# v2.net
KiCad netlist of a schematic drawn in EAGLE
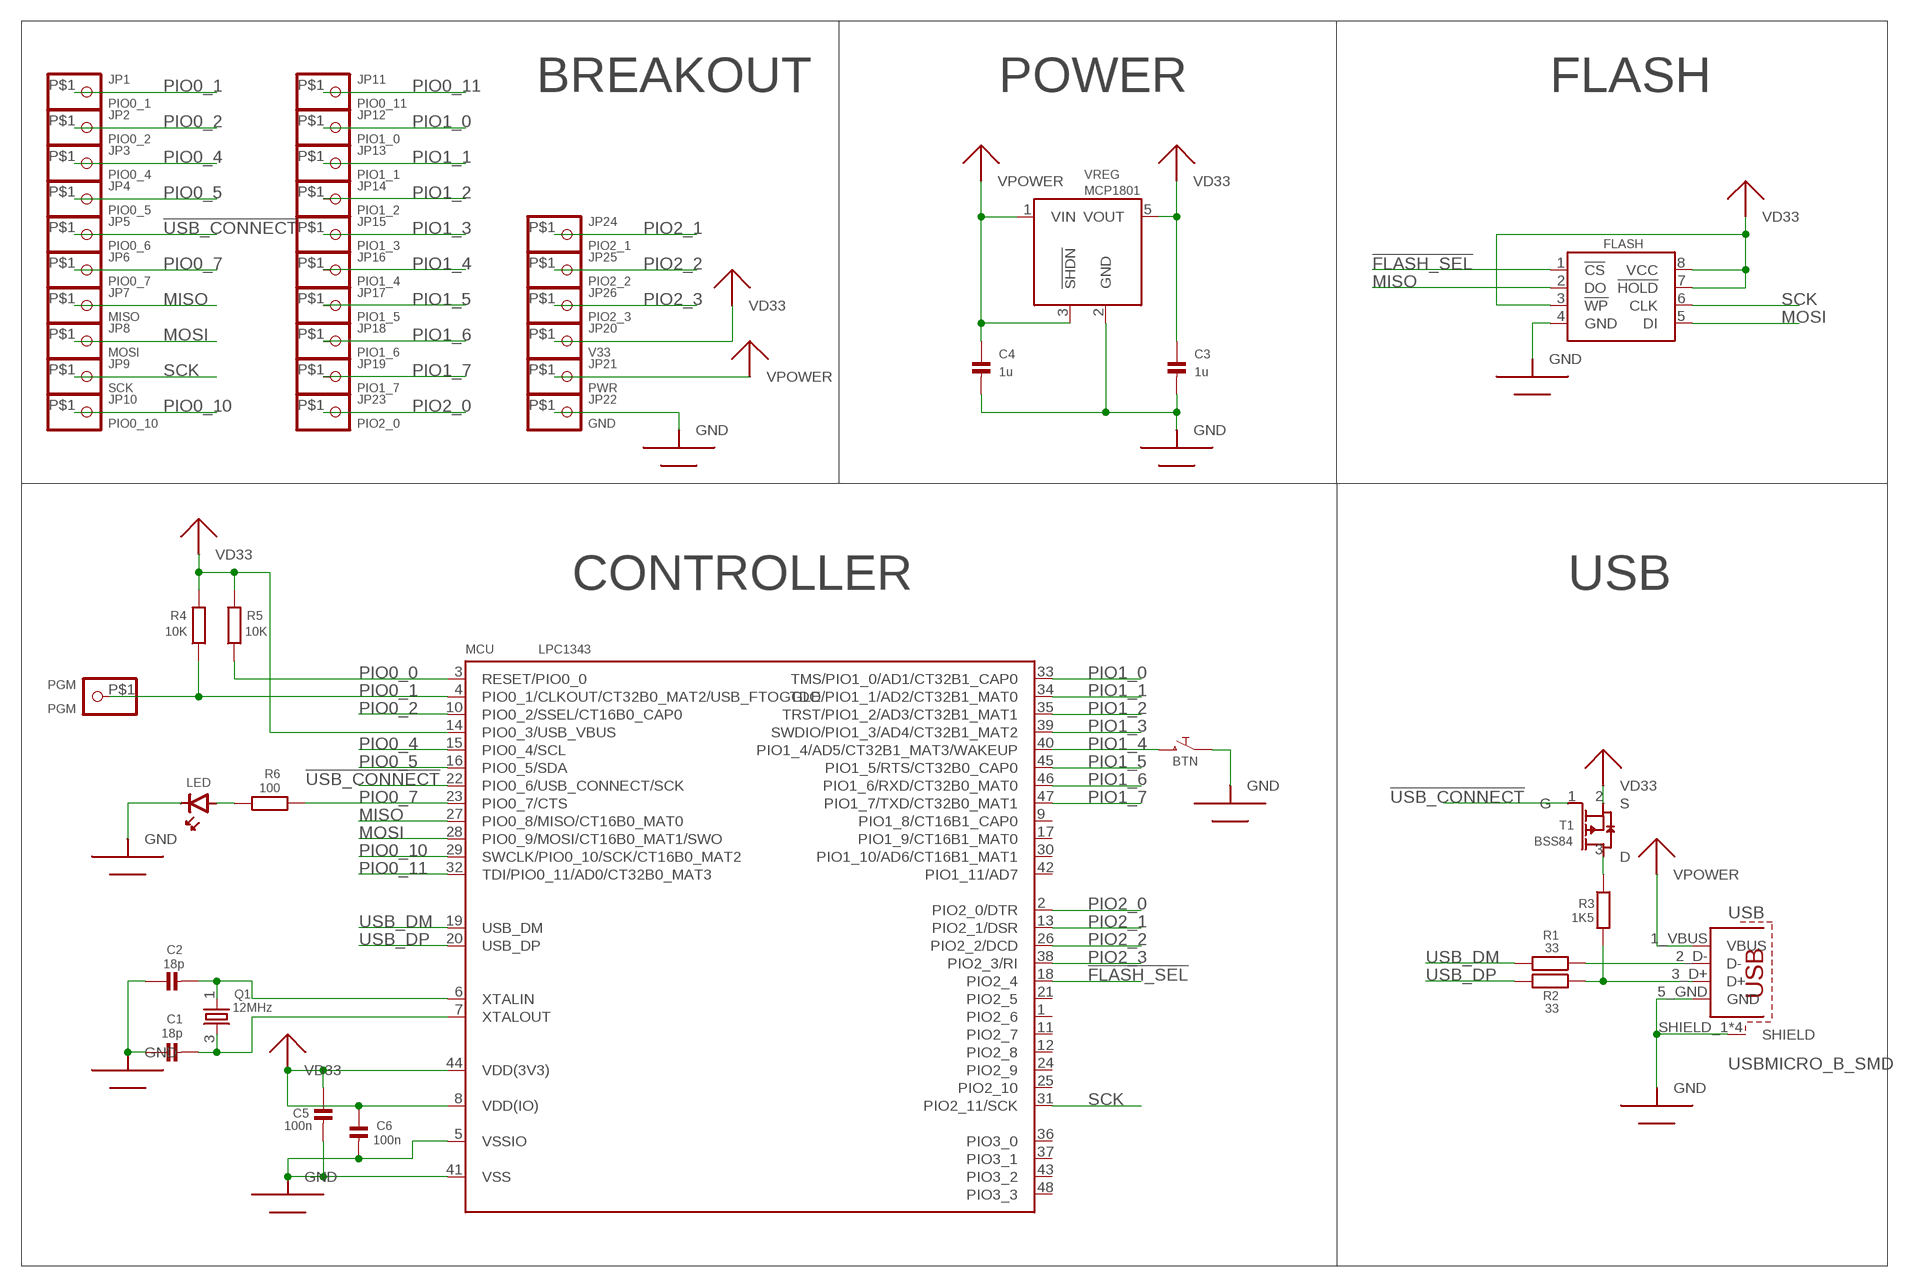
[diagram p0: schematic, sheet 1]

(export (version "E")
  (design (tool "Eeschema 10.0.6"))
  (components
    (comp (ref "BTN")
      (value "PUSHBUTTONEVQP0")
      (footprint "eagle-import:EVQP0")
      (libsource (lib "eagle-import") (part "PUSHBUTTONEVQP0"))
    )
    (comp (ref "C1")
      (value "18p")
      (footprint "eagle-import:0805_MICROMELF_COMBO")
      (libsource (lib "eagle-import") (part "CAP_CERAMIC0805_MICROMELF_COMBO"))
    )
    (comp (ref "C2")
      (value "18p")
      (footprint "eagle-import:0805_MICROMELF_COMBO")
      (libsource (lib "eagle-import") (part "CAP_CERAMIC0805_MICROMELF_COMBO"))
    )
    (comp (ref "C3")
      (value "1u")
      (footprint "eagle-import:0805_MICROMELF_COMBO")
      (libsource (lib "eagle-import") (part "CAP_CERAMIC0805_MICROMELF_COMBO"))
    )
    (comp (ref "C4")
      (value "1u")
      (footprint "eagle-import:0805_MICROMELF_COMBO")
      (libsource (lib "eagle-import") (part "CAP_CERAMIC0805_MICROMELF_COMBO"))
    )
    (comp (ref "C5")
      (value "100n")
      (footprint "eagle-import:0805_MICROMELF_COMBO")
      (libsource (lib "eagle-import") (part "CAP_CERAMIC0805_MICROMELF_COMBO"))
    )
    (comp (ref "C6")
      (value "100n")
      (footprint "eagle-import:0805_MICROMELF_COMBO")
      (libsource (lib "eagle-import") (part "CAP_CERAMIC0805_MICROMELF_COMBO"))
    )
    (comp (ref "FLASH")
      (value "SERIALFLASHSOIC8-150MIL")
      (footprint "eagle-import:SOIC8-150MIL")
      (libsource (lib "eagle-import") (part "SERIALFLASHSOIC8-150MIL"))
    )
    (comp (ref "JP1")
      (value "PIO0_1")
      (footprint "eagle-import:PCB_MEDIUM_RECT_PAD")
      (libsource (lib "eagle-import") (part "HEADER-1X1SMD_MEDIUM"))
    )
    (comp (ref "JP2")
      (value "PIO0_2")
      (footprint "eagle-import:PCB_MEDIUM_RECT_PAD")
      (libsource (lib "eagle-import") (part "HEADER-1X1SMD_MEDIUM"))
    )
    (comp (ref "JP3")
      (value "PIO0_4")
      (footprint "eagle-import:PCB_MEDIUM_RECT_PAD")
      (libsource (lib "eagle-import") (part "HEADER-1X1SMD_MEDIUM"))
    )
    (comp (ref "JP4")
      (value "PIO0_5")
      (footprint "eagle-import:PCB_MEDIUM_RECT_PAD")
      (libsource (lib "eagle-import") (part "HEADER-1X1SMD_MEDIUM"))
    )
    (comp (ref "JP5")
      (value "PIO0_6")
      (footprint "eagle-import:PCB_MEDIUM_RECT_PAD")
      (libsource (lib "eagle-import") (part "HEADER-1X1SMD_MEDIUM"))
    )
    (comp (ref "JP6")
      (value "PIO0_7")
      (footprint "eagle-import:PCB_MEDIUM_RECT_PAD")
      (libsource (lib "eagle-import") (part "HEADER-1X1SMD_MEDIUM"))
    )
    (comp (ref "JP7")
      (value "MISO")
      (footprint "eagle-import:PCB_MEDIUM_RECT_PAD")
      (libsource (lib "eagle-import") (part "HEADER-1X1SMD_MEDIUM"))
    )
    (comp (ref "JP8")
      (value "MOSI")
      (footprint "eagle-import:PCB_MEDIUM_RECT_PAD")
      (libsource (lib "eagle-import") (part "HEADER-1X1SMD_MEDIUM"))
    )
    (comp (ref "JP9")
      (value "SCK")
      (footprint "eagle-import:PCB_MEDIUM_RECT_PAD")
      (libsource (lib "eagle-import") (part "HEADER-1X1SMD_MEDIUM"))
    )
    (comp (ref "JP10")
      (value "PIO0_10")
      (footprint "eagle-import:PCB_MEDIUM_RECT_PAD")
      (libsource (lib "eagle-import") (part "HEADER-1X1SMD_MEDIUM"))
    )
    (comp (ref "JP11")
      (value "PIO0_11")
      (footprint "eagle-import:PCB_MEDIUM_RECT_PAD")
      (libsource (lib "eagle-import") (part "HEADER-1X1SMD_MEDIUM"))
    )
    (comp (ref "JP12")
      (value "PIO1_0")
      (footprint "eagle-import:PCB_MEDIUM_RECT_PAD")
      (libsource (lib "eagle-import") (part "HEADER-1X1SMD_MEDIUM"))
    )
    (comp (ref "JP13")
      (value "PIO1_1")
      (footprint "eagle-import:PCB_MEDIUM_RECT_PAD")
      (libsource (lib "eagle-import") (part "HEADER-1X1SMD_MEDIUM"))
    )
    (comp (ref "JP14")
      (value "PIO1_2")
      (footprint "eagle-import:PCB_MEDIUM_RECT_PAD")
      (libsource (lib "eagle-import") (part "HEADER-1X1SMD_MEDIUM"))
    )
    (comp (ref "JP15")
      (value "PIO1_3")
      (footprint "eagle-import:PCB_MEDIUM_RECT_PAD")
      (libsource (lib "eagle-import") (part "HEADER-1X1SMD_MEDIUM"))
    )
    (comp (ref "JP16")
      (value "PIO1_4")
      (footprint "eagle-import:PCB_MEDIUM_RECT_PAD")
      (libsource (lib "eagle-import") (part "HEADER-1X1SMD_MEDIUM"))
    )
    (comp (ref "JP17")
      (value "PIO1_5")
      (footprint "eagle-import:PCB_MEDIUM_RECT_PAD")
      (libsource (lib "eagle-import") (part "HEADER-1X1SMD_MEDIUM"))
    )
    (comp (ref "JP18")
      (value "PIO1_6")
      (footprint "eagle-import:PCB_MEDIUM_RECT_PAD")
      (libsource (lib "eagle-import") (part "HEADER-1X1SMD_MEDIUM"))
    )
    (comp (ref "JP19")
      (value "PIO1_7")
      (footprint "eagle-import:PCB_MEDIUM_RECT_PAD")
      (libsource (lib "eagle-import") (part "HEADER-1X1SMD_MEDIUM"))
    )
    (comp (ref "JP20")
      (value "V33")
      (footprint "eagle-import:PCB_MEDIUM_RECT_PAD")
      (libsource (lib "eagle-import") (part "HEADER-1X1SMD_MEDIUM"))
    )
    (comp (ref "JP21")
      (value "PWR")
      (footprint "eagle-import:PCB_MEDIUM_RECT_PAD")
      (libsource (lib "eagle-import") (part "HEADER-1X1SMD_MEDIUM"))
    )
    (comp (ref "JP22")
      (value "GND")
      (footprint "eagle-import:PCB_MEDIUM_RECT_PAD")
      (libsource (lib "eagle-import") (part "HEADER-1X1SMD_MEDIUM"))
    )
    (comp (ref "JP23")
      (value "PIO2_0")
      (footprint "eagle-import:PCB_MEDIUM_RECT_PAD")
      (libsource (lib "eagle-import") (part "HEADER-1X1SMD_MEDIUM"))
    )
    (comp (ref "JP24")
      (value "PIO2_1")
      (footprint "eagle-import:PCB_MEDIUM_RECT_PAD")
      (libsource (lib "eagle-import") (part "HEADER-1X1SMD_MEDIUM"))
    )
    (comp (ref "JP25")
      (value "PIO2_2")
      (footprint "eagle-import:PCB_MEDIUM_RECT_PAD")
      (libsource (lib "eagle-import") (part "HEADER-1X1SMD_MEDIUM"))
    )
    (comp (ref "JP26")
      (value "PIO2_3")
      (footprint "eagle-import:PCB_MEDIUM_RECT_PAD")
      (libsource (lib "eagle-import") (part "HEADER-1X1SMD_MEDIUM"))
    )
    (comp (ref "LED")
      (value "LED0805")
      (footprint "eagle-import:0805_POLAR")
      (libsource (lib "eagle-import") (part "LED0805"))
    )
    (comp (ref "MCU")
      (value "LPC1343")
      (footprint "eagle-import:LQFP48")
      (libsource (lib "eagle-import") (part "LPC1343_QFP"))
    )
    (comp (ref "PGM")
      (value "PGM")
      (footprint "eagle-import:PCB_MEDIUM_RECT_PAD")
      (libsource (lib "eagle-import") (part "HEADER-1X1SMD_MEDIUM"))
    )
    (comp (ref "Q1")
      (value "12MHz")
      (footprint "eagle-import:ABM8G")
      (libsource (lib "eagle-import") (part "QUARTZABM8G"))
    )
    (comp (ref "R1")
      (value "33")
      (footprint "eagle-import:0805_MICROMELF_COMBO")
      (libsource (lib "eagle-import") (part "R-EU_0805_MICROMELF_COMBO"))
    )
    (comp (ref "R2")
      (value "33")
      (footprint "eagle-import:0805_MICROMELF_COMBO")
      (libsource (lib "eagle-import") (part "R-EU_0805_MICROMELF_COMBO"))
    )
    (comp (ref "R3")
      (value "1K5")
      (footprint "eagle-import:0805_MICROMELF_COMBO")
      (libsource (lib "eagle-import") (part "R-EU_0805_MICROMELF_COMBO"))
    )
    (comp (ref "R4")
      (value "10K")
      (footprint "eagle-import:0805_MICROMELF_COMBO")
      (libsource (lib "eagle-import") (part "R-EU_0805_MICROMELF_COMBO"))
    )
    (comp (ref "R5")
      (value "10K")
      (footprint "eagle-import:0805_MICROMELF_COMBO")
      (libsource (lib "eagle-import") (part "R-EU_0805_MICROMELF_COMBO"))
    )
    (comp (ref "R6")
      (value "100")
      (footprint "eagle-import:0805_MICROMELF_COMBO")
      (libsource (lib "eagle-import") (part "R-EU_0805_MICROMELF_COMBO"))
    )
    (comp (ref "T1")
      (value "BSS84")
      (footprint "eagle-import:SOT23")
      (libsource (lib "eagle-import") (part "PMOS_ENH"))
    )
    (comp (ref "USB")
      (value "USBMICRO_B_SMD")
      (footprint "eagle-import:MICRO_USB_B_SMD")
      (libsource (lib "eagle-import") (part "USBMICRO_B_SMD"))
    )
    (comp (ref "VREG")
      (value "MCP1801")
      (footprint "eagle-import:SOT-23-5")
      (libsource (lib "eagle-import") (part "MCP180XSOT-23-5"))
    )
  )
  (nets
    (net (code "1") (name "/MISO") (class "Default")
      (node (ref "FLASH") (pin "2") (pinfunction "DO_2") (pintype "output"))
      (node (ref "JP7") (pin "P$1") (pinfunction "1_P$1") (pintype "passive"))
      (node (ref "MCU") (pin "27") (pinfunction "PIO0_8/MISO/CT16B0_MAT0_27") (pintype "bidirectional"))
    )
    (net (code "2") (name "/MOSI") (class "Default")
      (node (ref "FLASH") (pin "5") (pinfunction "DI_5") (pintype "input"))
      (node (ref "JP8") (pin "P$1") (pinfunction "1_P$1") (pintype "passive"))
      (node (ref "MCU") (pin "28") (pinfunction "PIO0_9/MOSI/CT16B0_MAT1/SWO_28") (pintype "bidirectional"))
    )
    (net (code "3") (name "/PIO0_0") (class "Default")
      (node (ref "MCU") (pin "3") (pinfunction "RESET/PIO0_0_3") (pintype "bidirectional"))
      (node (ref "R5") (pin "1") (pinfunction "1_1") (pintype "passive"))
    )
    (net (code "4") (name "/PIO0_1") (class "Default")
      (node (ref "JP1") (pin "P$1") (pinfunction "1_P$1") (pintype "passive"))
      (node (ref "MCU") (pin "4") (pinfunction "PIO0_1/CLKOUT/CT32B0_MAT2/USB_FTOGGLE_4") (pintype "bidirectional"))
      (node (ref "PGM") (pin "P$1") (pinfunction "1_P$1") (pintype "passive"))
      (node (ref "R4") (pin "1") (pinfunction "1_1") (pintype "passive"))
    )
    (net (code "5") (name "/PIO0_2") (class "Default")
      (node (ref "JP2") (pin "P$1") (pinfunction "1_P$1") (pintype "passive"))
      (node (ref "MCU") (pin "10") (pinfunction "PIO0_2/SSEL/CT16B0_CAP0_10") (pintype "bidirectional"))
    )
    (net (code "6") (name "/PIO0_4") (class "Default")
      (node (ref "JP3") (pin "P$1") (pinfunction "1_P$1") (pintype "passive"))
      (node (ref "MCU") (pin "15") (pinfunction "PIO0_4/SCL_15") (pintype "bidirectional"))
    )
    (net (code "7") (name "/PIO0_5") (class "Default")
      (node (ref "JP4") (pin "P$1") (pinfunction "1_P$1") (pintype "passive"))
      (node (ref "MCU") (pin "16") (pinfunction "PIO0_5/SDA_16") (pintype "bidirectional"))
    )
    (net (code "8") (name "/PIO0_7") (class "Default")
      (node (ref "JP6") (pin "P$1") (pinfunction "1_P$1") (pintype "passive"))
      (node (ref "MCU") (pin "23") (pinfunction "PIO0_7/CTS_23") (pintype "bidirectional"))
      (node (ref "R6") (pin "2") (pinfunction "2_2") (pintype "passive"))
    )
    (net (code "9") (name "/PIO0_10") (class "Default")
      (node (ref "JP10") (pin "P$1") (pinfunction "1_P$1") (pintype "passive"))
      (node (ref "MCU") (pin "29") (pinfunction "SWCLK/PIO0_10/SCK/CT16B0_MAT2_29") (pintype "bidirectional"))
    )
    (net (code "10") (name "/PIO0_11") (class "Default")
      (node (ref "JP11") (pin "P$1") (pinfunction "1_P$1") (pintype "passive"))
      (node (ref "MCU") (pin "32") (pinfunction "TDI/PIO0_11/AD0/CT32B0_MAT3_32") (pintype "bidirectional"))
    )
    (net (code "11") (name "/PIO1_0") (class "Default")
      (node (ref "JP12") (pin "P$1") (pinfunction "1_P$1") (pintype "passive"))
      (node (ref "MCU") (pin "33") (pinfunction "TMS/PIO1_0/AD1/CT32B1_CAP0_33") (pintype "bidirectional"))
    )
    (net (code "12") (name "/PIO1_1") (class "Default")
      (node (ref "JP13") (pin "P$1") (pinfunction "1_P$1") (pintype "passive"))
      (node (ref "MCU") (pin "34") (pinfunction "TDO/PIO1_1/AD2/CT32B1_MAT0_34") (pintype "bidirectional"))
    )
    (net (code "13") (name "/PIO1_2") (class "Default")
      (node (ref "JP14") (pin "P$1") (pinfunction "1_P$1") (pintype "passive"))
      (node (ref "MCU") (pin "35") (pinfunction "TRST/PIO1_2/AD3/CT32B1_MAT1_35") (pintype "bidirectional"))
    )
    (net (code "14") (name "/PIO1_3") (class "Default")
      (node (ref "JP15") (pin "P$1") (pinfunction "1_P$1") (pintype "passive"))
      (node (ref "MCU") (pin "39") (pinfunction "SWDIO/PIO1_3/AD4/CT32B1_MAT2_39") (pintype "bidirectional"))
    )
    (net (code "15") (name "/PIO1_4") (class "Default")
      (node (ref "BTN") (pin "B") (pinfunction "2_B") (pintype "bidirectional"))
      (node (ref "JP16") (pin "P$1") (pinfunction "1_P$1") (pintype "passive"))
      (node (ref "MCU") (pin "40") (pinfunction "PIO1_4/AD5/CT32B1_MAT3/WAKEUP_40") (pintype "bidirectional"))
    )
    (net (code "16") (name "/PIO1_5") (class "Default")
      (node (ref "JP17") (pin "P$1") (pinfunction "1_P$1") (pintype "passive"))
      (node (ref "MCU") (pin "45") (pinfunction "PIO1_5/RTS/CT32B0_CAP0_45") (pintype "bidirectional"))
    )
    (net (code "17") (name "/PIO1_6") (class "Default")
      (node (ref "JP18") (pin "P$1") (pinfunction "1_P$1") (pintype "passive"))
      (node (ref "MCU") (pin "46") (pinfunction "PIO1_6/RXD/CT32B0_MAT0_46") (pintype "bidirectional"))
    )
    (net (code "18") (name "/PIO1_7") (class "Default")
      (node (ref "JP19") (pin "P$1") (pinfunction "1_P$1") (pintype "passive"))
      (node (ref "MCU") (pin "47") (pinfunction "PIO1_7/TXD/CT32B0_MAT1_47") (pintype "bidirectional"))
    )
    (net (code "19") (name "/PIO2_0") (class "Default")
      (node (ref "JP23") (pin "P$1") (pinfunction "1_P$1") (pintype "passive"))
      (node (ref "MCU") (pin "2") (pinfunction "PIO2_0/DTR_2") (pintype "bidirectional"))
    )
    (net (code "20") (name "/PIO2_1") (class "Default")
      (node (ref "JP24") (pin "P$1") (pinfunction "1_P$1") (pintype "passive"))
      (node (ref "MCU") (pin "13") (pinfunction "PIO2_1/DSR_13") (pintype "bidirectional"))
    )
    (net (code "21") (name "/PIO2_2") (class "Default")
      (node (ref "JP25") (pin "P$1") (pinfunction "1_P$1") (pintype "passive"))
      (node (ref "MCU") (pin "26") (pinfunction "PIO2_2/DCD_26") (pintype "bidirectional"))
    )
    (net (code "22") (name "/PIO2_3") (class "Default")
      (node (ref "JP26") (pin "P$1") (pinfunction "1_P$1") (pintype "passive"))
      (node (ref "MCU") (pin "38") (pinfunction "PIO2_3/RI_38") (pintype "bidirectional"))
    )
    (net (code "23") (name "/SCK") (class "Default")
      (node (ref "FLASH") (pin "6") (pinfunction "CLK_6") (pintype "input"))
      (node (ref "JP9") (pin "P$1") (pinfunction "1_P$1") (pintype "passive"))
      (node (ref "MCU") (pin "31") (pinfunction "PIO2_11/SCK_31") (pintype "bidirectional"))
    )
    (net (code "24") (name "/USB_DM") (class "Default")
      (node (ref "MCU") (pin "19") (pinfunction "USB_DM_19") (pintype "bidirectional"))
      (node (ref "R1") (pin "2") (pinfunction "2_2") (pintype "passive"))
    )
    (net (code "25") (name "/USB_DP") (class "Default")
      (node (ref "MCU") (pin "20") (pinfunction "USB_DP_20") (pintype "bidirectional"))
      (node (ref "R2") (pin "2") (pinfunction "2_2") (pintype "passive"))
    )
    (net (code "26") (name "/~{FLASH_SEL}") (class "Default")
      (node (ref "FLASH") (pin "1") (pinfunction "~{CS}_1") (pintype "input"))
      (node (ref "MCU") (pin "18") (pinfunction "PIO2_4_18") (pintype "bidirectional"))
    )
    (net (code "27") (name "/~{USB_CONNECT}") (class "Default")
      (node (ref "JP5") (pin "P$1") (pinfunction "1_P$1") (pintype "passive"))
      (node (ref "MCU") (pin "22") (pinfunction "PIO0_6/USB_CONNECT/SCK_22") (pintype "bidirectional"))
      (node (ref "T1") (pin "1") (pinfunction "G_1") (pintype "bidirectional"))
    )
    (net (code "28") (name "GND") (class "Default")
      (node (ref "BTN") (pin "A") (pinfunction "1_A") (pintype "bidirectional"))
      (node (ref "C1") (pin "1") (pinfunction "P$1_1") (pintype "passive"))
      (node (ref "C2") (pin "1") (pinfunction "P$1_1") (pintype "passive"))
      (node (ref "C3") (pin "2") (pinfunction "P$2_2") (pintype "passive"))
      (node (ref "C4") (pin "2") (pinfunction "P$2_2") (pintype "passive"))
      (node (ref "C5") (pin "2") (pinfunction "P$2_2") (pintype "passive"))
      (node (ref "C6") (pin "2") (pinfunction "P$2_2") (pintype "passive"))
      (node (ref "FLASH") (pin "4") (pinfunction "GND_4") (pintype "power_in"))
      (node (ref "JP22") (pin "P$1") (pinfunction "1_P$1") (pintype "passive"))
      (node (ref "LED") (pin "K") (pinfunction "CATHODE_K") (pintype "bidirectional"))
      (node (ref "MCU") (pin "41") (pinfunction "VSS_41") (pintype "power_in"))
      (node (ref "MCU") (pin "5") (pinfunction "VSSIO_5") (pintype "power_in"))
      (node (ref "USB") (pin "5_GND") (pinfunction "GND_5_GND") (pintype "power_in"))
      (node (ref "USB") (pin "SHIELD_1") (pinfunction "SHIELD_SHIELD_1") (pintype "passive"))
      (node (ref "USB") (pin "SHIELD_2") (pinfunction "SHIELD_SHIELD_2") (pintype "passive"))
      (node (ref "USB") (pin "SHIELD_3") (pinfunction "SHIELD_SHIELD_3") (pintype "passive"))
      (node (ref "USB") (pin "SHIELD_4") (pinfunction "SHIELD_SHIELD_4") (pintype "passive"))
      (node (ref "VREG") (pin "2") (pinfunction "GND_2") (pintype "power_in"))
    )
    (net (code "29") (name "Net-(C1-P$2)") (class "Default")
      (node (ref "C1") (pin "2") (pinfunction "P$2_2") (pintype "passive"))
      (node (ref "MCU") (pin "7") (pinfunction "XTALOUT_7") (pintype "output"))
      (node (ref "Q1") (pin "3") (pinfunction "2_3") (pintype "passive"))
    )
    (net (code "30") (name "Net-(C2-P$2)") (class "Default")
      (node (ref "C2") (pin "2") (pinfunction "P$2_2") (pintype "passive"))
      (node (ref "MCU") (pin "6") (pinfunction "XTALIN_6") (pintype "input"))
      (node (ref "Q1") (pin "1") (pinfunction "1_1") (pintype "passive"))
    )
    (net (code "31") (name "Net-(LED-ANODE)") (class "Default")
      (node (ref "LED") (pin "A") (pinfunction "ANODE_A") (pintype "bidirectional"))
      (node (ref "R6") (pin "1") (pinfunction "1_1") (pintype "passive"))
    )
    (net (code "32") (name "Net-(T1-D)") (class "Default")
      (node (ref "R3") (pin "1") (pinfunction "1_1") (pintype "passive"))
      (node (ref "T1") (pin "3") (pinfunction "D_3") (pintype "bidirectional"))
    )
    (net (code "33") (name "Net-(USB-D+)") (class "Default")
      (node (ref "R2") (pin "1") (pinfunction "1_1") (pintype "passive"))
      (node (ref "R3") (pin "2") (pinfunction "2_2") (pintype "passive"))
      (node (ref "USB") (pin "3_D+") (pinfunction "D+_3_D+") (pintype "bidirectional"))
    )
    (net (code "34") (name "Net-(USB-D-)") (class "Default")
      (node (ref "R1") (pin "1") (pinfunction "1_1") (pintype "passive"))
      (node (ref "USB") (pin "2_D-") (pinfunction "D-_2_D-") (pintype "bidirectional"))
    )
    (net (code "35") (name "VD33") (class "Default")
      (node (ref "C3") (pin "1") (pinfunction "P$1_1") (pintype "passive"))
      (node (ref "C5") (pin "1") (pinfunction "P$1_1") (pintype "passive"))
      (node (ref "C6") (pin "1") (pinfunction "P$1_1") (pintype "passive"))
      (node (ref "FLASH") (pin "3") (pinfunction "~{WP}_3") (pintype "input"))
      (node (ref "FLASH") (pin "7") (pinfunction "~{HOLD}_7") (pintype "input"))
      (node (ref "FLASH") (pin "8") (pinfunction "VCC_8") (pintype "power_in"))
      (node (ref "JP20") (pin "P$1") (pinfunction "1_P$1") (pintype "passive"))
      (node (ref "MCU") (pin "14") (pinfunction "PIO0_3/USB_VBUS_14") (pintype "bidirectional"))
      (node (ref "MCU") (pin "44") (pinfunction "VDD(3V3)_44") (pintype "power_in"))
      (node (ref "MCU") (pin "8") (pinfunction "VDD(IO)_8") (pintype "power_in"))
      (node (ref "R4") (pin "2") (pinfunction "2_2") (pintype "passive"))
      (node (ref "R5") (pin "2") (pinfunction "2_2") (pintype "passive"))
      (node (ref "T1") (pin "2") (pinfunction "S_2") (pintype "bidirectional"))
      (node (ref "VREG") (pin "5") (pinfunction "VOUT_5") (pintype "power_in"))
    )
    (net (code "36") (name "VPOWER") (class "Default")
      (node (ref "C4") (pin "1") (pinfunction "P$1_1") (pintype "passive"))
      (node (ref "JP21") (pin "P$1") (pinfunction "1_P$1") (pintype "passive"))
      (node (ref "USB") (pin "1_VBUS") (pinfunction "VBUS_1_VBUS") (pintype "power_in"))
      (node (ref "VREG") (pin "1") (pinfunction "VIN_1") (pintype "power_in"))
      (node (ref "VREG") (pin "3") (pinfunction "~{SHDN}_3") (pintype "input"))
    )
    (net (code "37") (name "unconnected-(MCU-PIO1_8{slash}CT16B1_CAP0-Pad9)") (class "Default")
      (node (ref "MCU") (pin "9") (pinfunction "PIO1_8/CT16B1_CAP0_9") (pintype "bidirectional"))
    )
    (net (code "38") (name "unconnected-(MCU-PIO1_9{slash}CT16B1_MAT0-Pad17)") (class "Default")
      (node (ref "MCU") (pin "17") (pinfunction "PIO1_9/CT16B1_MAT0_17") (pintype "bidirectional"))
    )
    (net (code "39") (name "unconnected-(MCU-PIO1_10{slash}AD6{slash}CT16B1_MAT1-Pad30)") (class "Default")
      (node (ref "MCU") (pin "30") (pinfunction "PIO1_10/AD6/CT16B1_MAT1_30") (pintype "bidirectional"))
    )
    (net (code "40") (name "unconnected-(MCU-PIO1_11{slash}AD7-Pad42)") (class "Default")
      (node (ref "MCU") (pin "42") (pinfunction "PIO1_11/AD7_42") (pintype "bidirectional"))
    )
    (net (code "41") (name "unconnected-(MCU-PIO2_5-Pad21)") (class "Default")
      (node (ref "MCU") (pin "21") (pinfunction "PIO2_5_21") (pintype "bidirectional"))
    )
    (net (code "42") (name "unconnected-(MCU-PIO2_6-Pad1)") (class "Default")
      (node (ref "MCU") (pin "1") (pinfunction "PIO2_6_1") (pintype "bidirectional"))
    )
    (net (code "43") (name "unconnected-(MCU-PIO2_7-Pad11)") (class "Default")
      (node (ref "MCU") (pin "11") (pinfunction "PIO2_7_11") (pintype "bidirectional"))
    )
    (net (code "44") (name "unconnected-(MCU-PIO2_8-Pad12)") (class "Default")
      (node (ref "MCU") (pin "12") (pinfunction "PIO2_8_12") (pintype "bidirectional"))
    )
    (net (code "45") (name "unconnected-(MCU-PIO2_9-Pad24)") (class "Default")
      (node (ref "MCU") (pin "24") (pinfunction "PIO2_9_24") (pintype "bidirectional"))
    )
    (net (code "46") (name "unconnected-(MCU-PIO2_10-Pad25)") (class "Default")
      (node (ref "MCU") (pin "25") (pinfunction "PIO2_10_25") (pintype "bidirectional"))
    )
    (net (code "47") (name "unconnected-(MCU-PIO3_0-Pad36)") (class "Default")
      (node (ref "MCU") (pin "36") (pinfunction "PIO3_0_36") (pintype "bidirectional"))
    )
    (net (code "48") (name "unconnected-(MCU-PIO3_1-Pad37)") (class "Default")
      (node (ref "MCU") (pin "37") (pinfunction "PIO3_1_37") (pintype "bidirectional"))
    )
    (net (code "49") (name "unconnected-(MCU-PIO3_2-Pad43)") (class "Default")
      (node (ref "MCU") (pin "43") (pinfunction "PIO3_2_43") (pintype "bidirectional"))
    )
    (net (code "50") (name "unconnected-(MCU-PIO3_3-Pad48)") (class "Default")
      (node (ref "MCU") (pin "48") (pinfunction "PIO3_3_48") (pintype "bidirectional"))
    )
  )
)
